# MMA8452Q_Breakout.net
KiCad netlist of a schematic drawn in EAGLE
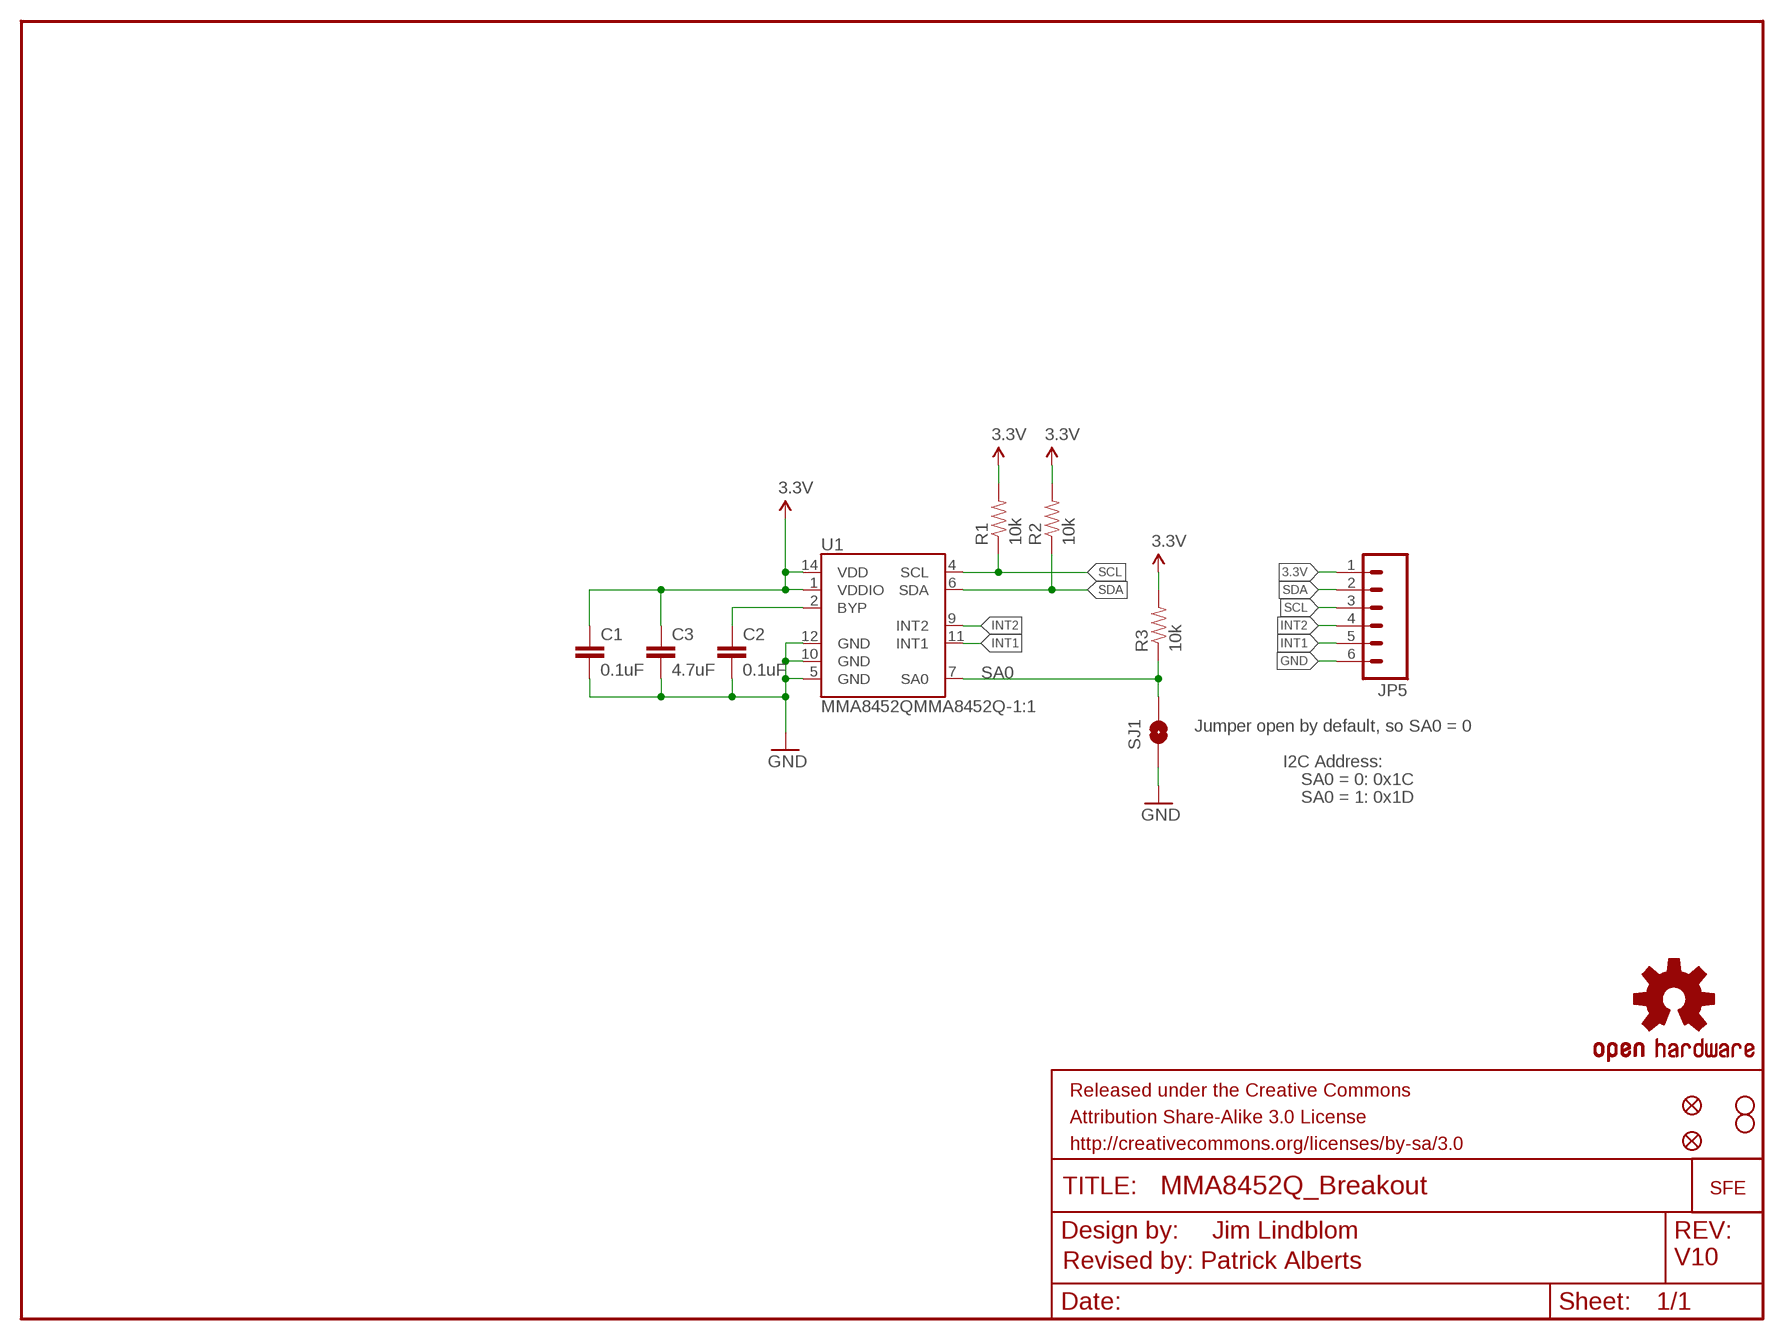
[diagram p0: schematic, sheet 1]

(export (version "E")
  (design (tool "Eeschema 10.0.6"))
  (components
    (comp (ref "C1")
      (value "0.1uF")
      (footprint "eagle-import:0603-CAP")
      (libsource (lib "eagle-import") (part "0.1UF-25V(+80/-20%)(0603)"))
    )
    (comp (ref "C2")
      (value "0.1uF")
      (footprint "eagle-import:0603-CAP")
      (libsource (lib "eagle-import") (part "0.1UF-25V(+80/-20%)(0603)"))
    )
    (comp (ref "C3")
      (value "4.7uF")
      (footprint "eagle-import:0603-CAP")
      (libsource (lib "eagle-import") (part "4.7UF-6.3V-10%(0603)0603"))
    )
    (comp (ref "FID1")
      (value "FIDUCIAL1X2")
      (footprint "eagle-import:FIDUCIAL-1X2")
      (libsource (lib "eagle-import") (part "FIDUCIAL1X2"))
    )
    (comp (ref "FID2")
      (value "FIDUCIAL1X2")
      (footprint "eagle-import:FIDUCIAL-1X2")
      (libsource (lib "eagle-import") (part "FIDUCIAL1X2"))
    )
    (comp (ref "FRAME1")
      (value "FRAME-LETTER")
      (footprint "eagle-import:CREATIVE_COMMONS")
      (libsource (lib "eagle-import") (part "FRAME-LETTER"))
    )
    (comp (ref "JP1")
      (value "LOGO-SFESK")
      (footprint "eagle-import:SFE-LOGO-FLAME")
      (libsource (lib "eagle-import") (part "LOGO-SFESK"))
    )
    (comp (ref "JP3")
      (value "STAND-OFF")
      (footprint "eagle-import:STAND-OFF")
      (libsource (lib "eagle-import") (part "STAND-OFF"))
    )
    (comp (ref "JP4")
      (value "STAND-OFF")
      (footprint "eagle-import:STAND-OFF")
      (libsource (lib "eagle-import") (part "STAND-OFF"))
    )
    (comp (ref "JP5")
      (value "M06SIP")
      (footprint "eagle-import:1X06")
      (libsource (lib "eagle-import") (part "M06SIP"))
    )
    (comp (ref "R1")
      (value "10k")
      (footprint "eagle-import:0603-RES")
      (libsource (lib "eagle-import") (part "10K-1%RES-00824"))
    )
    (comp (ref "R2")
      (value "10k")
      (footprint "eagle-import:0603-RES")
      (libsource (lib "eagle-import") (part "10K-1%RES-00824"))
    )
    (comp (ref "R3")
      (value "10k")
      (footprint "eagle-import:0603-RES")
      (libsource (lib "eagle-import") (part "10K-1%RES-00824"))
    )
    (comp (ref "SJ1")
      (value "SOLDERJUMPERNO")
      (footprint "eagle-import:SJ_2S-NO")
      (libsource (lib "eagle-import") (part "SOLDERJUMPERNO"))
    )
    (comp (ref "U$1")
      (value "OSHW-LOGOS")
      (footprint "eagle-import:OSHW-LOGO-S")
      (libsource (lib "eagle-import") (part "OSHW-LOGOS"))
    )
    (comp (ref "U1")
      (value "MMA8452QMMA8452Q-1:1")
      (footprint "eagle-import:MMA8452Q-1_1")
      (libsource (lib "eagle-import") (part "MMA8452QMMA8452Q-1{colon}1"))
    )
  )
  (nets
    (net (code "1") (name "/SA0") (class "Default")
      (node (ref "R3") (pin "1") (pinfunction "1_1") (pintype "passive"))
      (node (ref "SJ1") (pin "2") (pinfunction "2_2") (pintype "passive"))
      (node (ref "U1") (pin "7") (pinfunction "SA0_7") (pintype "bidirectional"))
    )
    (net (code "2") (name "3.3V") (class "Default")
      (node (ref "C1") (pin "1") (pinfunction "1_1") (pintype "passive"))
      (node (ref "C3") (pin "1") (pinfunction "1_1") (pintype "passive"))
      (node (ref "JP5") (pin "1") (pinfunction "1_1") (pintype "passive"))
      (node (ref "R1") (pin "2") (pinfunction "2_2") (pintype "passive"))
      (node (ref "R2") (pin "2") (pinfunction "2_2") (pintype "passive"))
      (node (ref "R3") (pin "2") (pinfunction "2_2") (pintype "passive"))
      (node (ref "U1") (pin "1") (pinfunction "VDDIO_1") (pintype "bidirectional"))
      (node (ref "U1") (pin "14") (pinfunction "VDD_14") (pintype "bidirectional"))
    )
    (net (code "3") (name "GND") (class "Default")
      (node (ref "C1") (pin "2") (pinfunction "2_2") (pintype "passive"))
      (node (ref "C2") (pin "2") (pinfunction "2_2") (pintype "passive"))
      (node (ref "C3") (pin "2") (pinfunction "2_2") (pintype "passive"))
      (node (ref "JP5") (pin "6") (pinfunction "6_6") (pintype "passive"))
      (node (ref "SJ1") (pin "1") (pinfunction "1_1") (pintype "passive"))
      (node (ref "U1") (pin "10") (pinfunction "GND_10") (pintype "bidirectional"))
      (node (ref "U1") (pin "12") (pinfunction "GND_12") (pintype "bidirectional"))
      (node (ref "U1") (pin "5") (pinfunction "GND_5") (pintype "bidirectional"))
    )
    (net (code "4") (name "INT1") (class "Default")
      (node (ref "JP5") (pin "5") (pinfunction "5_5") (pintype "passive"))
      (node (ref "U1") (pin "11") (pinfunction "INT1_11") (pintype "bidirectional"))
    )
    (net (code "5") (name "INT2") (class "Default")
      (node (ref "JP5") (pin "4") (pinfunction "4_4") (pintype "passive"))
      (node (ref "U1") (pin "9") (pinfunction "INT2_9") (pintype "bidirectional"))
    )
    (net (code "6") (name "Net-(U1-BYP)") (class "Default")
      (node (ref "C2") (pin "1") (pinfunction "1_1") (pintype "passive"))
      (node (ref "U1") (pin "2") (pinfunction "BYP_2") (pintype "bidirectional"))
    )
    (net (code "7") (name "SCL") (class "Default")
      (node (ref "JP5") (pin "3") (pinfunction "3_3") (pintype "passive"))
      (node (ref "R1") (pin "1") (pinfunction "1_1") (pintype "passive"))
      (node (ref "U1") (pin "4") (pinfunction "SCL_4") (pintype "bidirectional"))
    )
    (net (code "8") (name "SDA") (class "Default")
      (node (ref "JP5") (pin "2") (pinfunction "2_2") (pintype "passive"))
      (node (ref "R2") (pin "1") (pinfunction "1_1") (pintype "passive"))
      (node (ref "U1") (pin "6") (pinfunction "SDA_6") (pintype "bidirectional"))
    )
  )
)
